# clock_driver_board.net
KiCad netlist of a schematic drawn in EAGLE
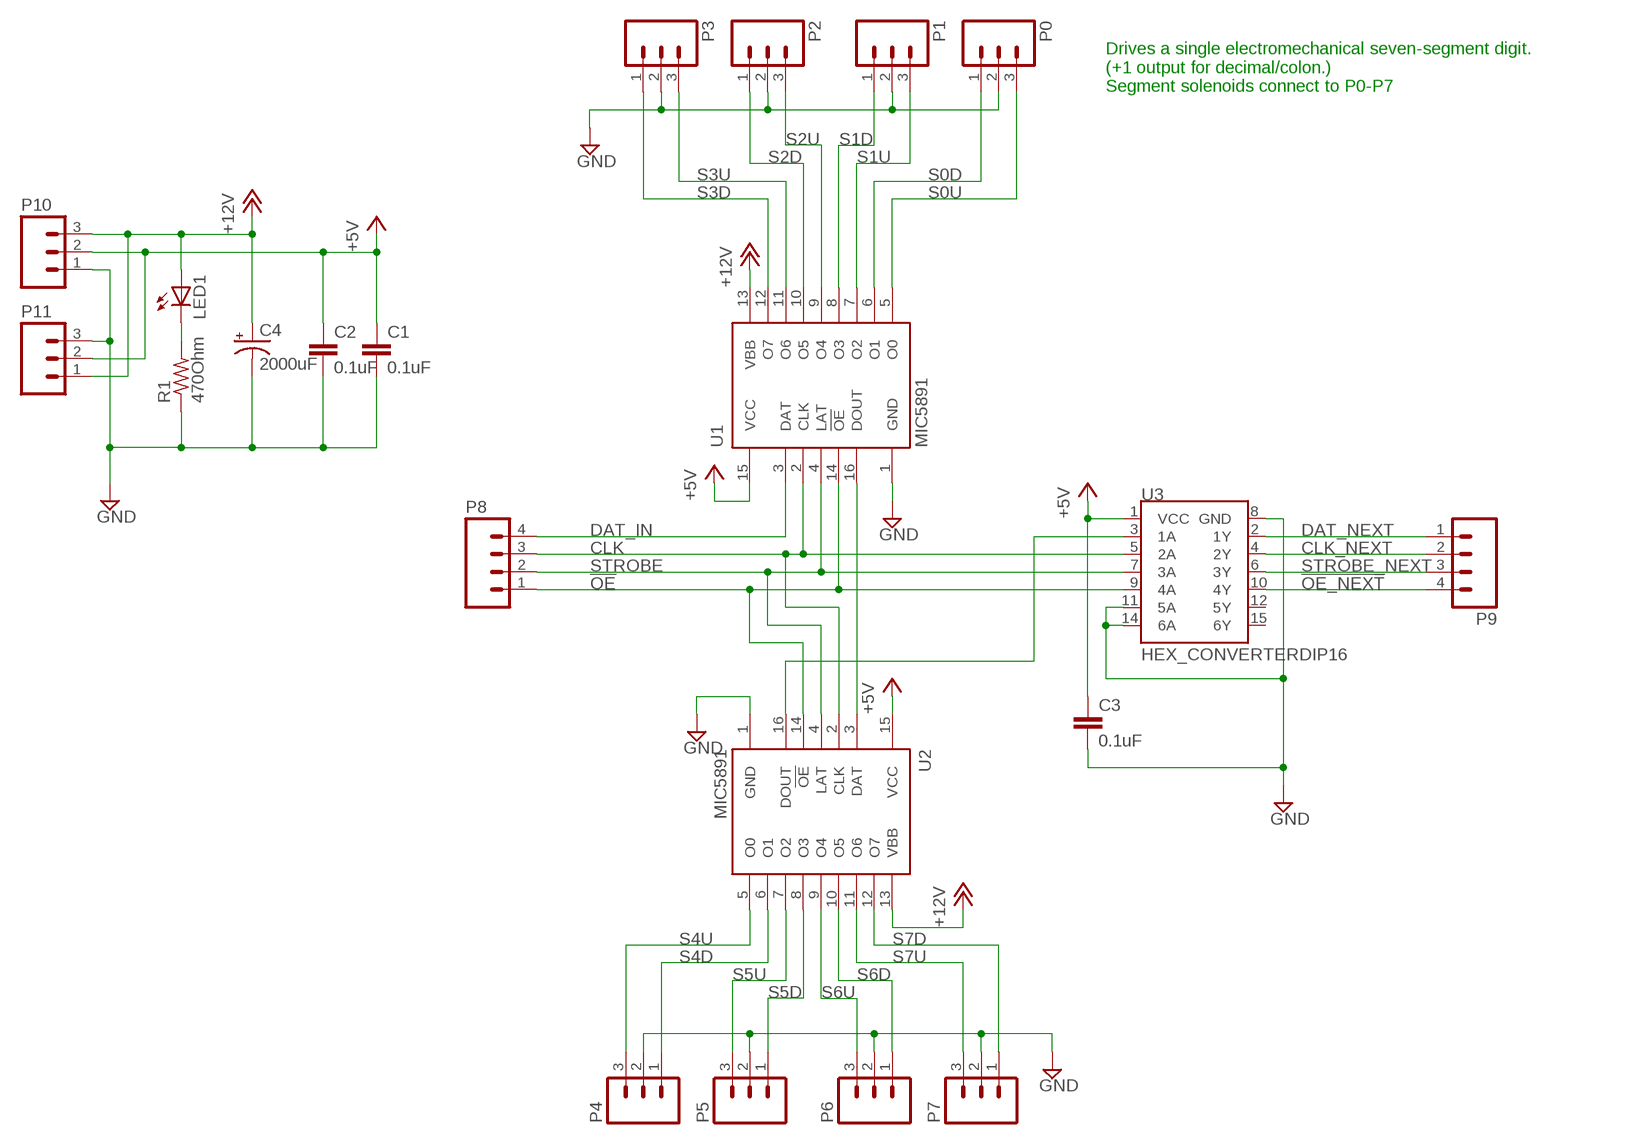
[diagram p0: schematic, sheet 1]

(export (version "E")
  (design (tool "Eeschema 10.0.6"))
  (components
    (comp (ref "C1")
      (value "0.1uF")
      (footprint "eagle-import:C2.5-2")
      (fields (field (name "PARTNO") "21RZ310-RC"))
      (libsource (lib "eagle-import") (part "C2.5/2"))
    )
    (comp (ref "C2")
      (value "0.1uF")
      (footprint "eagle-import:C2.5-2")
      (fields (field (name "PARTNO") "21RZ310-RC"))
      (libsource (lib "eagle-import") (part "C2.5/2"))
    )
    (comp (ref "C3")
      (value "0.1uF")
      (footprint "eagle-import:C2.5-2")
      (fields (field (name "PARTNO") "21RZ310-RC"))
      (libsource (lib "eagle-import") (part "C2.5/2"))
    )
    (comp (ref "C4")
      (value "2000uF")
      (footprint "eagle-import:E7,5-16")
      (fields (field (name "PARTNO") "EEU-TP1E202S"))
      (libsource (lib "eagle-import") (part "CPOL-USE7.5-16"))
    )
    (comp (ref "LED1")
      (value "LED3MM")
      (footprint "eagle-import:LED3MM")
      (fields (field (name "PARTNO") "WP7113SRD/D"))
      (libsource (lib "eagle-import") (part "LED3MM"))
    )
    (comp (ref "P0")
      (value "M03LONGPADS")
      (footprint "eagle-import:1X03_LONGPADS")
      (libsource (lib "eagle-import") (part "M03LONGPADS"))
    )
    (comp (ref "P1")
      (value "M03LONGPADS")
      (footprint "eagle-import:1X03_LONGPADS")
      (libsource (lib "eagle-import") (part "M03LONGPADS"))
    )
    (comp (ref "P2")
      (value "M03LONGPADS")
      (footprint "eagle-import:1X03_LONGPADS")
      (libsource (lib "eagle-import") (part "M03LONGPADS"))
    )
    (comp (ref "P3")
      (value "M03LONGPADS")
      (footprint "eagle-import:1X03_LONGPADS")
      (libsource (lib "eagle-import") (part "M03LONGPADS"))
    )
    (comp (ref "P4")
      (value "M03LONGPADS")
      (footprint "eagle-import:1X03_LONGPADS")
      (libsource (lib "eagle-import") (part "M03LONGPADS"))
    )
    (comp (ref "P5")
      (value "M03LONGPADS")
      (footprint "eagle-import:1X03_LONGPADS")
      (libsource (lib "eagle-import") (part "M03LONGPADS"))
    )
    (comp (ref "P6")
      (value "M03LONGPADS")
      (footprint "eagle-import:1X03_LONGPADS")
      (libsource (lib "eagle-import") (part "M03LONGPADS"))
    )
    (comp (ref "P7")
      (value "M03LONGPADS")
      (footprint "eagle-import:1X03_LONGPADS")
      (libsource (lib "eagle-import") (part "M03LONGPADS"))
    )
    (comp (ref "P8")
      (value "M04LONGPADS")
      (footprint "eagle-import:1X04_LONGPADS")
      (fields (field (name "PARTNO") "826631-4"))
      (libsource (lib "eagle-import") (part "M04LONGPADS"))
    )
    (comp (ref "P9")
      (value "M04LONGPADS")
      (footprint "eagle-import:1X04_LONGPADS")
      (fields (field (name "PARTNO") "826631-4"))
      (libsource (lib "eagle-import") (part "M04LONGPADS"))
    )
    (comp (ref "P10")
      (value "M03SCREW")
      (footprint "eagle-import:SCREWTERMINAL-3.5MM-3")
      (fields (field (name "PARTNO") "1546551-3"))
      (libsource (lib "eagle-import") (part "M03SCREW"))
    )
    (comp (ref "P11")
      (value "M03SCREW")
      (footprint "eagle-import:SCREWTERMINAL-3.5MM-3")
      (fields (field (name "PARTNO") "1546551-3"))
      (libsource (lib "eagle-import") (part "M03SCREW"))
    )
    (comp (ref "R1")
      (value "470Ohm")
      (footprint "eagle-import:0204_7")
      (fields (field (name "PARTNO") "CFR-25JR-52-470R"))
      (libsource (lib "eagle-import") (part "R-US_0204/7"))
    )
    (comp (ref "U1")
      (value "MIC5891")
      (footprint "eagle-import:DIL16")
      (fields (field (name "PARTNO") "MIC5891YN"))
      (libsource (lib "eagle-import") (part "MIC5891"))
    )
    (comp (ref "U2")
      (value "MIC5891")
      (footprint "eagle-import:DIL16")
      (fields (field (name "PARTNO") "MIC5891YN"))
      (libsource (lib "eagle-import") (part "MIC5891"))
    )
    (comp (ref "U3")
      (value "HEX_CONVERTERDIP16")
      (footprint "eagle-import:DIL16")
      (fields (field (name "PARTNO") "CD74HC4050E"))
      (libsource (lib "eagle-import") (part "HEX_CONVERTERDIP16"))
    )
  )
  (nets
    (net (code "1") (name "+5V") (class "Default")
      (node (ref "C1") (pin "1") (pinfunction "1_1") (pintype "passive"))
      (node (ref "C2") (pin "1") (pinfunction "1_1") (pintype "passive"))
      (node (ref "C3") (pin "1") (pinfunction "1_1") (pintype "passive"))
      (node (ref "P10") (pin "2") (pinfunction "2_2") (pintype "passive"))
      (node (ref "P11") (pin "2") (pinfunction "2_2") (pintype "passive"))
      (node (ref "U1") (pin "15") (pinfunction "VCC_15") (pintype "power_in"))
      (node (ref "U2") (pin "15") (pinfunction "VCC_15") (pintype "power_in"))
      (node (ref "U3") (pin "1") (pinfunction "VCC_1") (pintype "bidirectional"))
    )
    (net (code "2") (name "+12V") (class "Default")
      (node (ref "C4") (pin "+") (pinfunction "+_+") (pintype "passive"))
      (node (ref "LED1") (pin "A") (pinfunction "A_A") (pintype "passive"))
      (node (ref "P10") (pin "3") (pinfunction "3_3") (pintype "passive"))
      (node (ref "P11") (pin "1") (pinfunction "1_1") (pintype "passive"))
      (node (ref "U1") (pin "13") (pinfunction "VBB_13") (pintype "power_in"))
      (node (ref "U2") (pin "13") (pinfunction "VBB_13") (pintype "power_in"))
    )
    (net (code "3") (name "/CLK") (class "Default")
      (node (ref "P8") (pin "3") (pinfunction "3_3") (pintype "passive"))
      (node (ref "U1") (pin "2") (pinfunction "CLK_2") (pintype "bidirectional"))
      (node (ref "U2") (pin "2") (pinfunction "CLK_2") (pintype "bidirectional"))
      (node (ref "U3") (pin "5") (pinfunction "2A_5") (pintype "bidirectional"))
    )
    (net (code "4") (name "/CLK_NEXT") (class "Default")
      (node (ref "P9") (pin "2") (pinfunction "2_2") (pintype "passive"))
      (node (ref "U3") (pin "4") (pinfunction "2Y_4") (pintype "bidirectional"))
    )
    (net (code "5") (name "/DAT_IN") (class "Default")
      (node (ref "P8") (pin "4") (pinfunction "4_4") (pintype "passive"))
      (node (ref "U1") (pin "3") (pinfunction "DAT_3") (pintype "input"))
    )
    (net (code "6") (name "/DAT_NEXT") (class "Default")
      (node (ref "P9") (pin "1") (pinfunction "1_1") (pintype "passive"))
      (node (ref "U3") (pin "2") (pinfunction "1Y_2") (pintype "bidirectional"))
    )
    (net (code "7") (name "/S0D") (class "Default")
      (node (ref "P0") (pin "1") (pinfunction "1_1") (pintype "passive"))
      (node (ref "U1") (pin "6") (pinfunction "O1_6") (pintype "bidirectional"))
    )
    (net (code "8") (name "/S0U") (class "Default")
      (node (ref "P0") (pin "3") (pinfunction "3_3") (pintype "passive"))
      (node (ref "U1") (pin "5") (pinfunction "O0_5") (pintype "bidirectional"))
    )
    (net (code "9") (name "/S1D") (class "Default")
      (node (ref "P1") (pin "1") (pinfunction "1_1") (pintype "passive"))
      (node (ref "U1") (pin "8") (pinfunction "O3_8") (pintype "bidirectional"))
    )
    (net (code "10") (name "/S1U") (class "Default")
      (node (ref "P1") (pin "3") (pinfunction "3_3") (pintype "passive"))
      (node (ref "U1") (pin "7") (pinfunction "O2_7") (pintype "bidirectional"))
    )
    (net (code "11") (name "/S2D") (class "Default")
      (node (ref "P2") (pin "1") (pinfunction "1_1") (pintype "passive"))
      (node (ref "U1") (pin "10") (pinfunction "O5_10") (pintype "bidirectional"))
    )
    (net (code "12") (name "/S2U") (class "Default")
      (node (ref "P2") (pin "3") (pinfunction "3_3") (pintype "passive"))
      (node (ref "U1") (pin "9") (pinfunction "O4_9") (pintype "bidirectional"))
    )
    (net (code "13") (name "/S3D") (class "Default")
      (node (ref "P3") (pin "1") (pinfunction "1_1") (pintype "passive"))
      (node (ref "U1") (pin "12") (pinfunction "O7_12") (pintype "bidirectional"))
    )
    (net (code "14") (name "/S3U") (class "Default")
      (node (ref "P3") (pin "3") (pinfunction "3_3") (pintype "passive"))
      (node (ref "U1") (pin "11") (pinfunction "O6_11") (pintype "bidirectional"))
    )
    (net (code "15") (name "/S4D") (class "Default")
      (node (ref "P4") (pin "1") (pinfunction "1_1") (pintype "passive"))
      (node (ref "U2") (pin "6") (pinfunction "O1_6") (pintype "bidirectional"))
    )
    (net (code "16") (name "/S4U") (class "Default")
      (node (ref "P4") (pin "3") (pinfunction "3_3") (pintype "passive"))
      (node (ref "U2") (pin "5") (pinfunction "O0_5") (pintype "bidirectional"))
    )
    (net (code "17") (name "/S5D") (class "Default")
      (node (ref "P5") (pin "1") (pinfunction "1_1") (pintype "passive"))
      (node (ref "U2") (pin "8") (pinfunction "O3_8") (pintype "bidirectional"))
    )
    (net (code "18") (name "/S5U") (class "Default")
      (node (ref "P5") (pin "3") (pinfunction "3_3") (pintype "passive"))
      (node (ref "U2") (pin "7") (pinfunction "O2_7") (pintype "bidirectional"))
    )
    (net (code "19") (name "/S6D") (class "Default")
      (node (ref "P6") (pin "1") (pinfunction "1_1") (pintype "passive"))
      (node (ref "U2") (pin "10") (pinfunction "O5_10") (pintype "bidirectional"))
    )
    (net (code "20") (name "/S6U") (class "Default")
      (node (ref "P6") (pin "3") (pinfunction "3_3") (pintype "passive"))
      (node (ref "U2") (pin "9") (pinfunction "O4_9") (pintype "bidirectional"))
    )
    (net (code "21") (name "/S7D") (class "Default")
      (node (ref "P7") (pin "1") (pinfunction "1_1") (pintype "passive"))
      (node (ref "U2") (pin "12") (pinfunction "O7_12") (pintype "bidirectional"))
    )
    (net (code "22") (name "/S7U") (class "Default")
      (node (ref "P7") (pin "3") (pinfunction "3_3") (pintype "passive"))
      (node (ref "U2") (pin "11") (pinfunction "O6_11") (pintype "bidirectional"))
    )
    (net (code "23") (name "/STROBE") (class "Default")
      (node (ref "P8") (pin "2") (pinfunction "2_2") (pintype "passive"))
      (node (ref "U1") (pin "4") (pinfunction "LAT_4") (pintype "bidirectional"))
      (node (ref "U2") (pin "4") (pinfunction "LAT_4") (pintype "bidirectional"))
      (node (ref "U3") (pin "7") (pinfunction "3A_7") (pintype "bidirectional"))
    )
    (net (code "24") (name "/STROBE_NEXT") (class "Default")
      (node (ref "P9") (pin "3") (pinfunction "3_3") (pintype "passive"))
      (node (ref "U3") (pin "6") (pinfunction "3Y_6") (pintype "bidirectional"))
    )
    (net (code "25") (name "/~{OE_NEXT}") (class "Default")
      (node (ref "P9") (pin "4") (pinfunction "4_4") (pintype "passive"))
      (node (ref "U3") (pin "10") (pinfunction "4Y_10") (pintype "bidirectional"))
    )
    (net (code "26") (name "/~{OE}") (class "Default")
      (node (ref "P8") (pin "1") (pinfunction "1_1") (pintype "passive"))
      (node (ref "U1") (pin "14") (pinfunction "~{OE}_14") (pintype "bidirectional"))
      (node (ref "U2") (pin "14") (pinfunction "~{OE}_14") (pintype "bidirectional"))
      (node (ref "U3") (pin "9") (pinfunction "4A_9") (pintype "bidirectional"))
    )
    (net (code "27") (name "GND") (class "Default")
      (node (ref "C1") (pin "2") (pinfunction "2_2") (pintype "passive"))
      (node (ref "C2") (pin "2") (pinfunction "2_2") (pintype "passive"))
      (node (ref "C3") (pin "2") (pinfunction "2_2") (pintype "passive"))
      (node (ref "C4") (pin "-") (pinfunction "-_-") (pintype "passive"))
      (node (ref "P0") (pin "2") (pinfunction "2_2") (pintype "passive"))
      (node (ref "P1") (pin "2") (pinfunction "2_2") (pintype "passive"))
      (node (ref "P10") (pin "1") (pinfunction "1_1") (pintype "passive"))
      (node (ref "P11") (pin "3") (pinfunction "3_3") (pintype "passive"))
      (node (ref "P2") (pin "2") (pinfunction "2_2") (pintype "passive"))
      (node (ref "P3") (pin "2") (pinfunction "2_2") (pintype "passive"))
      (node (ref "P4") (pin "2") (pinfunction "2_2") (pintype "passive"))
      (node (ref "P5") (pin "2") (pinfunction "2_2") (pintype "passive"))
      (node (ref "P6") (pin "2") (pinfunction "2_2") (pintype "passive"))
      (node (ref "P7") (pin "2") (pinfunction "2_2") (pintype "passive"))
      (node (ref "R1") (pin "1") (pinfunction "1_1") (pintype "passive"))
      (node (ref "U1") (pin "1") (pinfunction "GND_1") (pintype "power_in"))
      (node (ref "U2") (pin "1") (pinfunction "GND_1") (pintype "power_in"))
      (node (ref "U3") (pin "11") (pinfunction "5A_11") (pintype "bidirectional"))
      (node (ref "U3") (pin "14") (pinfunction "6A_14") (pintype "bidirectional"))
      (node (ref "U3") (pin "8") (pinfunction "GND_8") (pintype "bidirectional"))
    )
    (net (code "28") (name "Net-(LED1-C)") (class "Default")
      (node (ref "LED1") (pin "K") (pinfunction "C_K") (pintype "passive"))
      (node (ref "R1") (pin "2") (pinfunction "2_2") (pintype "passive"))
    )
    (net (code "29") (name "Net-(U1-DOUT)") (class "Default")
      (node (ref "U1") (pin "16") (pinfunction "DOUT_16") (pintype "output"))
      (node (ref "U2") (pin "3") (pinfunction "DAT_3") (pintype "input"))
    )
    (net (code "30") (name "Net-(U2-DOUT)") (class "Default")
      (node (ref "U2") (pin "16") (pinfunction "DOUT_16") (pintype "output"))
      (node (ref "U3") (pin "3") (pinfunction "1A_3") (pintype "bidirectional"))
    )
    (net (code "31") (name "unconnected-(U3-5Y-Pad12)") (class "Default")
      (node (ref "U3") (pin "12") (pinfunction "5Y_12") (pintype "bidirectional"))
    )
    (net (code "32") (name "unconnected-(U3-6Y-Pad15)") (class "Default")
      (node (ref "U3") (pin "15") (pinfunction "6Y_15") (pintype "bidirectional"))
    )
  )
)
